# Connectors.net
KiCad netlist of a schematic drawn in Altium Designer
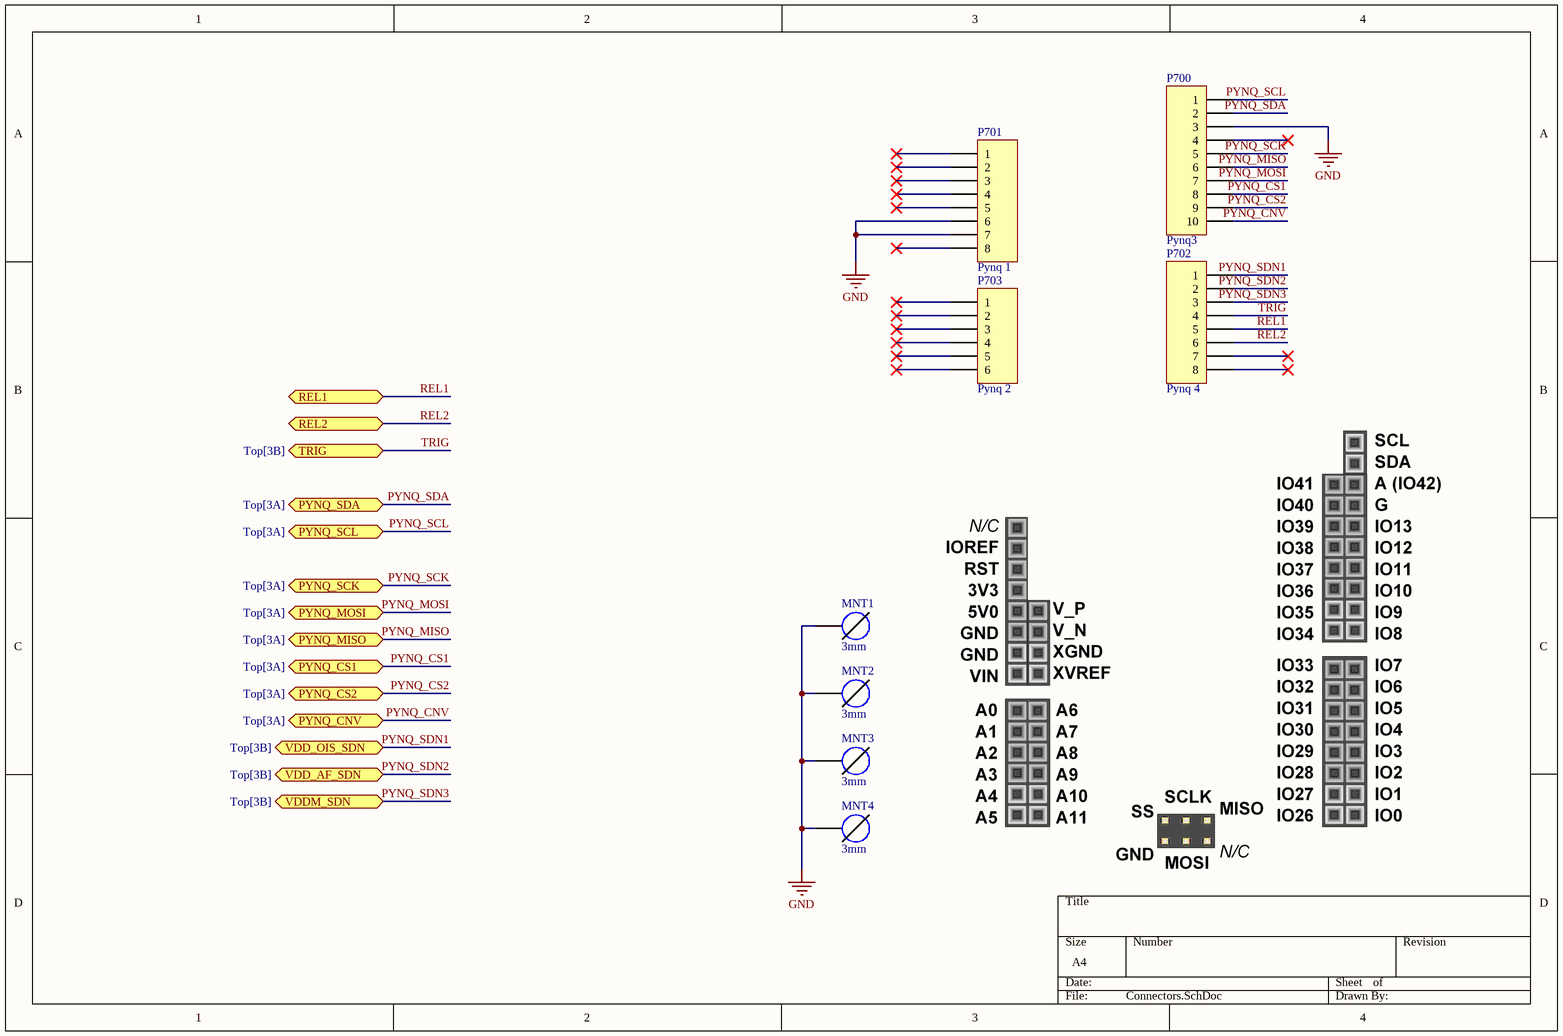
[diagram p0: Connectors.SchDoc]

(export (version "E")
  (design (tool "Eeschema 10.0.6"))
  (components
    (comp (ref "MNT1") (value "3mm") (footprint "3mm Hole") (libsource (lib "Hole") (part "Hole 3mm")))
    (comp (ref "MNT2") (value "3mm") (footprint "3mm Hole") (libsource (lib "Hole") (part "Hole 3mm")))
    (comp (ref "MNT3") (value "3mm") (footprint "3mm Hole") (libsource (lib "Hole") (part "Hole 3mm")))
    (comp (ref "MNT4") (value "3mm") (footprint "3mm Hole") (libsource (lib "Hole") (part "Hole 3mm")))
    (comp (ref "P700")
      (value "Pynq3")
      (footprint "HDR1X10")
      (description "Header, 10-Pin")
      (fields (field (name "PUBLISHER") "Altium Limited"))
      (libsource (lib "Miscellaneous Connectors") (part "Header 10"))
    )
    (comp (ref "P701")
      (value "Pynq 1")
      (footprint "HDR1X8")
      (description "Header, 8-Pin")
      (fields (field (name "PUBLISHER") "Altium Limited"))
      (libsource (lib "") (part "Header 8_1"))
    )
    (comp (ref "P702")
      (value "Pynq 4")
      (footprint "HDR1X8")
      (description "Header, 8-Pin")
      (fields (field (name "PUBLISHER") "Altium Limited"))
      (libsource (lib "Miscellaneous Connectors") (part "Header 8"))
    )
    (comp (ref "P703")
      (value "Pynq 2")
      (footprint "HDR1X6")
      (description "Header, 6-Pin")
      (fields (field (name "PUBLISHER") "Altium Limited"))
      (libsource (lib "Miscellaneous Connectors") (part "Header 6"))
    )
  )
  (nets
    (net (code "1") (name "/PYNQ_CNV") (class "Default")
      (node (ref "P700") (pin "10") (pinfunction "10_10") (pintype "passive"))
    )
    (net (code "2") (name "/PYNQ_CS1") (class "Default")
      (node (ref "P700") (pin "8") (pinfunction "8_8") (pintype "passive"))
    )
    (net (code "3") (name "/PYNQ_CS2") (class "Default")
      (node (ref "P700") (pin "9") (pinfunction "9_9") (pintype "passive"))
    )
    (net (code "4") (name "/PYNQ_MISO") (class "Default")
      (node (ref "P700") (pin "6") (pinfunction "6_6") (pintype "passive"))
    )
    (net (code "5") (name "/PYNQ_MOSI") (class "Default")
      (node (ref "P700") (pin "7") (pinfunction "7_7") (pintype "passive"))
    )
    (net (code "6") (name "/PYNQ_SCK") (class "Default")
      (node (ref "P700") (pin "5") (pinfunction "5_5") (pintype "passive"))
    )
    (net (code "7") (name "/PYNQ_SCL") (class "Default")
      (node (ref "P700") (pin "1") (pinfunction "1_1") (pintype "passive"))
    )
    (net (code "8") (name "/PYNQ_SDA") (class "Default")
      (node (ref "P700") (pin "2") (pinfunction "2_2") (pintype "passive"))
    )
    (net (code "9") (name "/PYNQ_SDN1") (class "Default")
      (node (ref "P702") (pin "1") (pinfunction "1_1") (pintype "passive"))
    )
    (net (code "10") (name "/PYNQ_SDN2") (class "Default")
      (node (ref "P702") (pin "2") (pinfunction "2_2") (pintype "passive"))
    )
    (net (code "11") (name "/PYNQ_SDN3") (class "Default")
      (node (ref "P702") (pin "3") (pinfunction "3_3") (pintype "passive"))
    )
    (net (code "12") (name "/REL1") (class "Default")
      (node (ref "P702") (pin "5") (pinfunction "5_5") (pintype "passive"))
    )
    (net (code "13") (name "/REL2") (class "Default")
      (node (ref "P702") (pin "6") (pinfunction "6_6") (pintype "passive"))
    )
    (net (code "14") (name "/TRIG") (class "Default")
      (node (ref "P702") (pin "4") (pinfunction "4_4") (pintype "passive"))
    )
    (net (code "15") (name "GND") (class "Default")
      (node (ref "MNT1") (pin "1") (pinfunction "1_1") (pintype "passive"))
      (node (ref "MNT2") (pin "1") (pinfunction "1_1") (pintype "passive"))
      (node (ref "MNT3") (pin "1") (pinfunction "1_1") (pintype "passive"))
      (node (ref "MNT4") (pin "1") (pinfunction "1_1") (pintype "passive"))
      (node (ref "P700") (pin "3") (pinfunction "3_3") (pintype "passive"))
      (node (ref "P701") (pin "6") (pinfunction "6_6") (pintype "passive"))
      (node (ref "P701") (pin "7") (pinfunction "7_7") (pintype "passive"))
    )
    (net (code "16") (name "unconnected-(P700-Pad4)") (class "Default")
      (node (ref "P700") (pin "4") (pinfunction "4_4") (pintype "passive+no_connect"))
    )
    (net (code "17") (name "unconnected-(P701-Pad1)") (class "Default")
      (node (ref "P701") (pin "1") (pinfunction "1_1") (pintype "passive+no_connect"))
    )
    (net (code "18") (name "unconnected-(P701-Pad2)") (class "Default")
      (node (ref "P701") (pin "2") (pinfunction "2_2") (pintype "passive+no_connect"))
    )
    (net (code "19") (name "unconnected-(P701-Pad3)") (class "Default")
      (node (ref "P701") (pin "3") (pinfunction "3_3") (pintype "passive+no_connect"))
    )
    (net (code "20") (name "unconnected-(P701-Pad4)") (class "Default")
      (node (ref "P701") (pin "4") (pinfunction "4_4") (pintype "passive+no_connect"))
    )
    (net (code "21") (name "unconnected-(P701-Pad5)") (class "Default")
      (node (ref "P701") (pin "5") (pinfunction "5_5") (pintype "passive+no_connect"))
    )
    (net (code "22") (name "unconnected-(P701-Pad8)") (class "Default")
      (node (ref "P701") (pin "8") (pinfunction "8_8") (pintype "passive+no_connect"))
    )
    (net (code "23") (name "unconnected-(P702-Pad7)") (class "Default")
      (node (ref "P702") (pin "7") (pinfunction "7_7") (pintype "passive+no_connect"))
    )
    (net (code "24") (name "unconnected-(P702-Pad8)") (class "Default")
      (node (ref "P702") (pin "8") (pinfunction "8_8") (pintype "passive+no_connect"))
    )
    (net (code "25") (name "unconnected-(P703-Pad1)") (class "Default")
      (node (ref "P703") (pin "1") (pinfunction "1_1") (pintype "passive+no_connect"))
    )
    (net (code "26") (name "unconnected-(P703-Pad2)") (class "Default")
      (node (ref "P703") (pin "2") (pinfunction "2_2") (pintype "passive+no_connect"))
    )
    (net (code "27") (name "unconnected-(P703-Pad3)") (class "Default")
      (node (ref "P703") (pin "3") (pinfunction "3_3") (pintype "passive+no_connect"))
    )
    (net (code "28") (name "unconnected-(P703-Pad4)") (class "Default")
      (node (ref "P703") (pin "4") (pinfunction "4_4") (pintype "passive+no_connect"))
    )
    (net (code "29") (name "unconnected-(P703-Pad5)") (class "Default")
      (node (ref "P703") (pin "5") (pinfunction "5_5") (pintype "passive+no_connect"))
    )
    (net (code "30") (name "unconnected-(P703-Pad6)") (class "Default")
      (node (ref "P703") (pin "6") (pinfunction "6_6") (pintype "passive+no_connect"))
    )
  )
)
